# LumSensor.net
KiCad netlist of a schematic drawn in Altium Designer
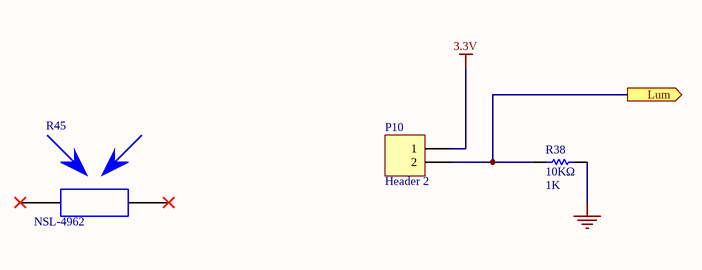
[diagram p0: LumSensor.SchDoc]

(export (version "E")
  (design (tool "Eeschema 10.0.6"))
  (components
    (comp (ref "P10")
      (value "Header 2")
      (footprint "BORNIER")
      (description "Header, 2-Pin")
      (fields
        (field (name "MANUFACTURER") "BUCHANAN - TE CONNECTIVITY")
        (field (name "PUBLISHER") "Altium Limited")
      )
      (libsource (lib "Miscellaneous Connectors") (part "Header 2"))
    )
    (comp (ref "R38")
      (value "10KΩ")
      (footprint "R0603")
      (description "Resistor")
      (fields
        (field (name "ALTIUM_VALUE") "1K")
        (field (name "MANUFACTURER") "MULTICOMP")
        (field (name "PUBLISHER") "Altium Limited")
      )
      (libsource (lib "Miscellaneous Devices") (part "Res1"))
    )
    (comp (ref "R45")
      (value "NSL-4962")
      (description "Ldr")
      (fields (field (name "MANUFACTURER") "ADVANCED PHOTONIX"))
      (libsource (lib "Electroplant") (part "NSL-4962"))
    )
  )
  (nets
    (net (code "1") (name "/Lum") (class "Default")
      (node (ref "P10") (pin "2") (pinfunction "2_2") (pintype "passive"))
      (node (ref "R38") (pin "1") (pinfunction "1_1") (pintype "passive"))
    )
    (net (code "2") (name "3.3V") (class "Default")
      (node (ref "P10") (pin "1") (pinfunction "1_1") (pintype "passive"))
    )
    (net (code "3") (name "GND") (class "Default")
      (node (ref "R38") (pin "2") (pinfunction "2_2") (pintype "passive"))
    )
    (net (code "4") (name "unconnected-(R45-Pad1)") (class "Default")
      (node (ref "R45") (pin "1") (pinfunction "1_1") (pintype "passive+no_connect"))
    )
    (net (code "5") (name "unconnected-(R45-Pad2)") (class "Default")
      (node (ref "R45") (pin "2") (pinfunction "2_2") (pintype "passive+no_connect"))
    )
  )
)
